# DI.net
KiCad netlist of a schematic drawn in Altium Designer
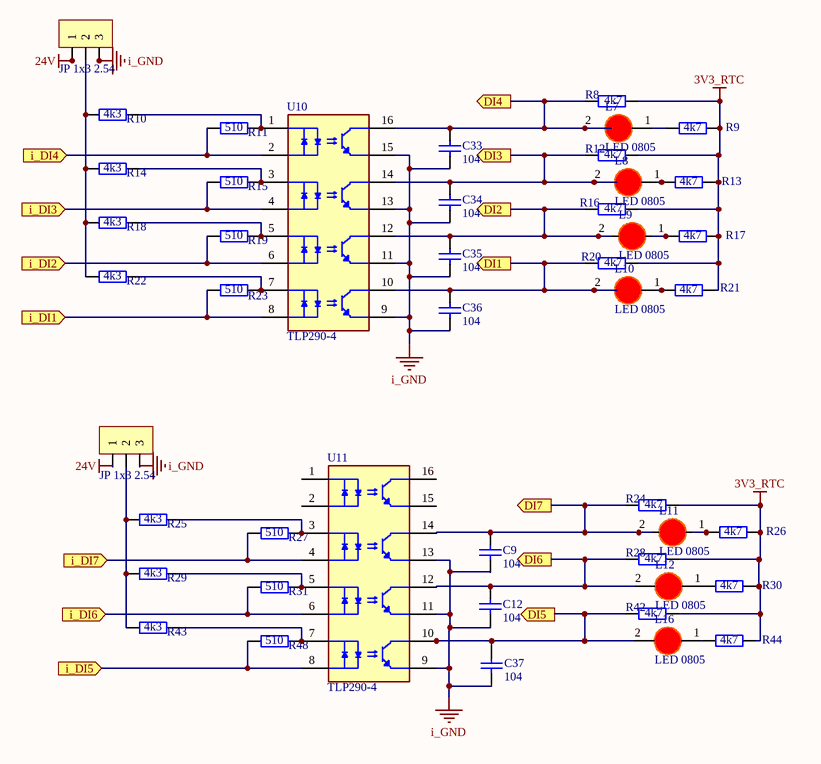
[diagram p0: DI.SchDoc]

(export (version "E")
  (design (tool "Eeschema 10.0.6"))
  (components
    (comp (ref "C9") (value "104") (footprint "0603_Cap") (libsource (lib "CMN") (part "Ceramic Capacitor")))
    (comp (ref "C12") (value "104") (footprint "0603_Cap") (libsource (lib "CMN") (part "Ceramic Capacitor")))
    (comp (ref "C33") (value "104") (footprint "0603_Cap") (libsource (lib "CMN") (part "Ceramic Capacitor")))
    (comp (ref "C34") (value "104") (footprint "0603_Cap") (libsource (lib "CMN") (part "Ceramic Capacitor")))
    (comp (ref "C35") (value "104") (footprint "0603_Cap") (libsource (lib "CMN") (part "Ceramic Capacitor")))
    (comp (ref "C36") (value "104") (footprint "0603_Cap") (libsource (lib "CMN") (part "Ceramic Capacitor")))
    (comp (ref "C37") (value "104") (footprint "0603_Cap") (libsource (lib "CMN") (part "Ceramic Capacitor")))
    (comp (ref "JP3")
      (value "JP 1x3 2.54")
      (footprint "JP 1x3 DT")
      (description "Cắm")
      (libsource (lib "Jump") (part "JP 1x3 2.54 Duc Thang"))
    )
    (comp (ref "JP4")
      (value "JP 1x3 2.54")
      (footprint "JP 1x3 DT")
      (description "Cắm")
      (libsource (lib "Jump") (part "JP 1x3 2.54 Duc Thang"))
    )
    (comp (ref "L7")
      (value "LED 0805")
      (footprint "LED-1206-Red")
      (description "Dán")
      (libsource (lib "Led") (part "LED 1206 Do"))
    )
    (comp (ref "L8")
      (value "LED 0805")
      (footprint "LED-1206-Red")
      (description "Dán")
      (libsource (lib "Led") (part "LED 1206 Do"))
    )
    (comp (ref "L9")
      (value "LED 0805")
      (footprint "LED-1206-Red")
      (description "Dán")
      (libsource (lib "Led") (part "LED 1206 Do"))
    )
    (comp (ref "L10")
      (value "LED 0805")
      (footprint "LED-1206-Red")
      (description "Dán")
      (libsource (lib "Led") (part "LED 1206 Do"))
    )
    (comp (ref "L11")
      (value "LED 0805")
      (footprint "LED-1206-Red")
      (description "Dán")
      (libsource (lib "Led") (part "LED 1206 Do"))
    )
    (comp (ref "L12")
      (value "LED 0805")
      (footprint "LED-1206-Red")
      (description "Dán")
      (libsource (lib "Led") (part "LED 1206 Do"))
    )
    (comp (ref "L16")
      (value "LED 0805")
      (footprint "LED-1206-Red")
      (description "Dán")
      (libsource (lib "Led") (part "LED 1206 Do"))
    )
    (comp (ref "R8") (value "4k7") (footprint "0603_Res") (libsource (lib "CMN") (part "Resistor")))
    (comp (ref "R9") (value "4k7") (footprint "0603_Res") (libsource (lib "CMN") (part "Resistor")))
    (comp (ref "R10") (value "4k3") (footprint "0603_Res") (libsource (lib "CMN") (part "Resistor")))
    (comp (ref "R11") (value "510") (footprint "0603_Res") (libsource (lib "CMN") (part "Resistor")))
    (comp (ref "R12") (value "4k7") (footprint "0603_Res") (libsource (lib "CMN") (part "Resistor")))
    (comp (ref "R13") (value "4k7") (footprint "0603_Res") (libsource (lib "CMN") (part "Resistor")))
    (comp (ref "R14") (value "4k3") (footprint "0603_Res") (libsource (lib "CMN") (part "Resistor")))
    (comp (ref "R15") (value "510") (footprint "0603_Res") (libsource (lib "CMN") (part "Resistor")))
    (comp (ref "R16") (value "4k7") (footprint "0603_Res") (libsource (lib "CMN") (part "Resistor")))
    (comp (ref "R17") (value "4k7") (footprint "0603_Res") (libsource (lib "CMN") (part "Resistor")))
    (comp (ref "R18") (value "4k3") (footprint "0603_Res") (libsource (lib "CMN") (part "Resistor")))
    (comp (ref "R19") (value "510") (footprint "0603_Res") (libsource (lib "CMN") (part "Resistor")))
    (comp (ref "R20") (value "4k7") (footprint "0603_Res") (libsource (lib "CMN") (part "Resistor")))
    (comp (ref "R21") (value "4k7") (footprint "0603_Res") (libsource (lib "CMN") (part "Resistor")))
    (comp (ref "R22") (value "4k3") (footprint "0603_Res") (libsource (lib "CMN") (part "Resistor")))
    (comp (ref "R23") (value "510") (footprint "0603_Res") (libsource (lib "CMN") (part "Resistor")))
    (comp (ref "R24") (value "4k7") (footprint "0603_Res") (libsource (lib "CMN") (part "Resistor")))
    (comp (ref "R25") (value "4k3") (footprint "0603_Res") (libsource (lib "CMN") (part "Resistor")))
    (comp (ref "R26") (value "4k7") (footprint "0603_Res") (libsource (lib "CMN") (part "Resistor")))
    (comp (ref "R27") (value "510") (footprint "0603_Res") (libsource (lib "CMN") (part "Resistor")))
    (comp (ref "R28") (value "4k7") (footprint "0603_Res") (libsource (lib "CMN") (part "Resistor")))
    (comp (ref "R29") (value "4k3") (footprint "0603_Res") (libsource (lib "CMN") (part "Resistor")))
    (comp (ref "R30") (value "4k7") (footprint "0603_Res") (libsource (lib "CMN") (part "Resistor")))
    (comp (ref "R31") (value "510") (footprint "0603_Res") (libsource (lib "CMN") (part "Resistor")))
    (comp (ref "R42") (value "4k7") (footprint "0603_Res") (libsource (lib "CMN") (part "Resistor")))
    (comp (ref "R43") (value "4k3") (footprint "0603_Res") (libsource (lib "CMN") (part "Resistor")))
    (comp (ref "R44") (value "4k7") (footprint "0603_Res") (libsource (lib "CMN") (part "Resistor")))
    (comp (ref "R48") (value "510") (footprint "0603_Res") (libsource (lib "CMN") (part "Resistor")))
    (comp (ref "U10")
      (value "TLP290-4")
      (footprint "OPTO_TLP290-4")
      (description "Optoisolator Transistor Output 2500Vrms 4 Channel 16-SO")
      (fields (field (name "MF") "Toshiba Semiconductor"))
      (libsource (lib "TLP290-4") (part "TLP290-4"))
    )
    (comp (ref "U11")
      (value "TLP290-4")
      (footprint "OPTO_TLP290-4")
      (description "Optoisolator Transistor Output 2500Vrms 4 Channel 16-SO")
      (fields (field (name "MF") "Toshiba Semiconductor"))
      (libsource (lib "TLP290-4") (part "TLP290-4"))
    )
  )
  (nets
    (net (code "1") (name "/DI1") (class "Default")
      (node (ref "C36") (pin "1") (pinfunction "1_1") (pintype "passive"))
      (node (ref "L10") (pin "2") (pinfunction "K_2") (pintype "passive"))
      (node (ref "R20") (pin "1") (pinfunction "1_1") (pintype "passive"))
      (node (ref "U10") (pin "10") (pinfunction "10_10") (pintype "passive"))
    )
    (net (code "2") (name "/DI2") (class "Default")
      (node (ref "C35") (pin "1") (pinfunction "1_1") (pintype "passive"))
      (node (ref "L9") (pin "2") (pinfunction "K_2") (pintype "passive"))
      (node (ref "R16") (pin "1") (pinfunction "1_1") (pintype "passive"))
      (node (ref "U10") (pin "12") (pinfunction "12_12") (pintype "passive"))
    )
    (net (code "3") (name "/DI3") (class "Default")
      (node (ref "C34") (pin "1") (pinfunction "1_1") (pintype "passive"))
      (node (ref "L8") (pin "2") (pinfunction "K_2") (pintype "passive"))
      (node (ref "R12") (pin "1") (pinfunction "1_1") (pintype "passive"))
      (node (ref "U10") (pin "14") (pinfunction "14_14") (pintype "passive"))
    )
    (net (code "4") (name "/DI4") (class "Default")
      (node (ref "C33") (pin "1") (pinfunction "1_1") (pintype "passive"))
      (node (ref "L7") (pin "2") (pinfunction "K_2") (pintype "passive"))
      (node (ref "R8") (pin "1") (pinfunction "1_1") (pintype "passive"))
      (node (ref "U10") (pin "16") (pinfunction "16_16") (pintype "passive"))
    )
    (net (code "5") (name "/DI5") (class "Default")
      (node (ref "C37") (pin "1") (pinfunction "1_1") (pintype "passive"))
      (node (ref "L16") (pin "2") (pinfunction "K_2") (pintype "passive"))
      (node (ref "R42") (pin "1") (pinfunction "1_1") (pintype "passive"))
      (node (ref "U11") (pin "10") (pinfunction "10_10") (pintype "passive"))
    )
    (net (code "6") (name "/DI6") (class "Default")
      (node (ref "C12") (pin "1") (pinfunction "1_1") (pintype "passive"))
      (node (ref "L12") (pin "2") (pinfunction "K_2") (pintype "passive"))
      (node (ref "R28") (pin "1") (pinfunction "1_1") (pintype "passive"))
      (node (ref "U11") (pin "12") (pinfunction "12_12") (pintype "passive"))
    )
    (net (code "7") (name "/DI7") (class "Default")
      (node (ref "C9") (pin "1") (pinfunction "1_1") (pintype "passive"))
      (node (ref "L11") (pin "2") (pinfunction "K_2") (pintype "passive"))
      (node (ref "R24") (pin "1") (pinfunction "1_1") (pintype "passive"))
      (node (ref "U11") (pin "14") (pinfunction "14_14") (pintype "passive"))
    )
    (net (code "8") (name "/i_DI1") (class "Default")
      (node (ref "R23") (pin "2") (pinfunction "2_2") (pintype "passive"))
      (node (ref "U10") (pin "8") (pinfunction "8_8") (pintype "passive"))
    )
    (net (code "9") (name "/i_DI2") (class "Default")
      (node (ref "R19") (pin "2") (pinfunction "2_2") (pintype "passive"))
      (node (ref "U10") (pin "6") (pinfunction "6_6") (pintype "passive"))
    )
    (net (code "10") (name "/i_DI3") (class "Default")
      (node (ref "R15") (pin "2") (pinfunction "2_2") (pintype "passive"))
      (node (ref "U10") (pin "4") (pinfunction "4_4") (pintype "passive"))
    )
    (net (code "11") (name "/i_DI4") (class "Default")
      (node (ref "R11") (pin "2") (pinfunction "2_2") (pintype "passive"))
      (node (ref "U10") (pin "2") (pinfunction "2_2") (pintype "passive"))
    )
    (net (code "12") (name "/i_DI5") (class "Default")
      (node (ref "R48") (pin "2") (pinfunction "2_2") (pintype "passive"))
      (node (ref "U11") (pin "8") (pinfunction "8_8") (pintype "passive"))
    )
    (net (code "13") (name "/i_DI6") (class "Default")
      (node (ref "R31") (pin "2") (pinfunction "2_2") (pintype "passive"))
      (node (ref "U11") (pin "6") (pinfunction "6_6") (pintype "passive"))
    )
    (net (code "14") (name "/i_DI7") (class "Default")
      (node (ref "R27") (pin "2") (pinfunction "2_2") (pintype "passive"))
      (node (ref "U11") (pin "4") (pinfunction "4_4") (pintype "passive"))
    )
    (net (code "15") (name "3V3_RTC") (class "Default")
      (node (ref "R12") (pin "2") (pinfunction "2_2") (pintype "passive"))
      (node (ref "R13") (pin "2") (pinfunction "2_2") (pintype "passive"))
      (node (ref "R16") (pin "2") (pinfunction "2_2") (pintype "passive"))
      (node (ref "R17") (pin "2") (pinfunction "2_2") (pintype "passive"))
      (node (ref "R20") (pin "2") (pinfunction "2_2") (pintype "passive"))
      (node (ref "R21") (pin "2") (pinfunction "2_2") (pintype "passive"))
      (node (ref "R24") (pin "2") (pinfunction "2_2") (pintype "passive"))
      (node (ref "R26") (pin "2") (pinfunction "2_2") (pintype "passive"))
      (node (ref "R28") (pin "2") (pinfunction "2_2") (pintype "passive"))
      (node (ref "R30") (pin "2") (pinfunction "2_2") (pintype "passive"))
      (node (ref "R42") (pin "2") (pinfunction "2_2") (pintype "passive"))
      (node (ref "R44") (pin "2") (pinfunction "2_2") (pintype "passive"))
      (node (ref "R8") (pin "2") (pinfunction "2_2") (pintype "passive"))
      (node (ref "R9") (pin "2") (pinfunction "2_2") (pintype "passive"))
    )
    (net (code "16") (name "24V") (class "Default")
      (node (ref "JP3") (pin "1") (pinfunction "1_1") (pintype "passive"))
      (node (ref "JP4") (pin "1") (pinfunction "1_1") (pintype "passive"))
    )
    (net (code "17") (name "Net-(JP3-Pad2)") (class "Default")
      (node (ref "JP3") (pin "2") (pinfunction "2_2") (pintype "passive"))
      (node (ref "R10") (pin "1") (pinfunction "1_1") (pintype "passive"))
      (node (ref "R14") (pin "1") (pinfunction "1_1") (pintype "passive"))
      (node (ref "R18") (pin "1") (pinfunction "1_1") (pintype "passive"))
      (node (ref "R22") (pin "1") (pinfunction "1_1") (pintype "passive"))
    )
    (net (code "18") (name "Net-(JP4-Pad2)") (class "Default")
      (node (ref "JP4") (pin "2") (pinfunction "2_2") (pintype "passive"))
      (node (ref "R25") (pin "1") (pinfunction "1_1") (pintype "passive"))
      (node (ref "R29") (pin "1") (pinfunction "1_1") (pintype "passive"))
      (node (ref "R43") (pin "1") (pinfunction "1_1") (pintype "passive"))
    )
    (net (code "19") (name "Net-(L7-A)") (class "Default")
      (node (ref "L7") (pin "1") (pinfunction "A_1") (pintype "passive"))
      (node (ref "R9") (pin "1") (pinfunction "1_1") (pintype "passive"))
    )
    (net (code "20") (name "Net-(L8-A)") (class "Default")
      (node (ref "L8") (pin "1") (pinfunction "A_1") (pintype "passive"))
      (node (ref "R13") (pin "1") (pinfunction "1_1") (pintype "passive"))
    )
    (net (code "21") (name "Net-(L9-A)") (class "Default")
      (node (ref "L9") (pin "1") (pinfunction "A_1") (pintype "passive"))
      (node (ref "R17") (pin "1") (pinfunction "1_1") (pintype "passive"))
    )
    (net (code "22") (name "Net-(L10-A)") (class "Default")
      (node (ref "L10") (pin "1") (pinfunction "A_1") (pintype "passive"))
      (node (ref "R21") (pin "1") (pinfunction "1_1") (pintype "passive"))
    )
    (net (code "23") (name "Net-(L11-A)") (class "Default")
      (node (ref "L11") (pin "1") (pinfunction "A_1") (pintype "passive"))
      (node (ref "R26") (pin "1") (pinfunction "1_1") (pintype "passive"))
    )
    (net (code "24") (name "Net-(L12-A)") (class "Default")
      (node (ref "L12") (pin "1") (pinfunction "A_1") (pintype "passive"))
      (node (ref "R30") (pin "1") (pinfunction "1_1") (pintype "passive"))
    )
    (net (code "25") (name "Net-(L16-A)") (class "Default")
      (node (ref "L16") (pin "1") (pinfunction "A_1") (pintype "passive"))
      (node (ref "R44") (pin "1") (pinfunction "1_1") (pintype "passive"))
    )
    (net (code "26") (name "Net-(R10-Pad2)") (class "Default")
      (node (ref "R10") (pin "2") (pinfunction "2_2") (pintype "passive"))
      (node (ref "R11") (pin "1") (pinfunction "1_1") (pintype "passive"))
      (node (ref "U10") (pin "1") (pinfunction "1_1") (pintype "passive"))
    )
    (net (code "27") (name "Net-(R14-Pad2)") (class "Default")
      (node (ref "R14") (pin "2") (pinfunction "2_2") (pintype "passive"))
      (node (ref "R15") (pin "1") (pinfunction "1_1") (pintype "passive"))
      (node (ref "U10") (pin "3") (pinfunction "3_3") (pintype "passive"))
    )
    (net (code "28") (name "Net-(R18-Pad2)") (class "Default")
      (node (ref "R18") (pin "2") (pinfunction "2_2") (pintype "passive"))
      (node (ref "R19") (pin "1") (pinfunction "1_1") (pintype "passive"))
      (node (ref "U10") (pin "5") (pinfunction "5_5") (pintype "passive"))
    )
    (net (code "29") (name "Net-(R22-Pad2)") (class "Default")
      (node (ref "R22") (pin "2") (pinfunction "2_2") (pintype "passive"))
      (node (ref "R23") (pin "1") (pinfunction "1_1") (pintype "passive"))
      (node (ref "U10") (pin "7") (pinfunction "7_7") (pintype "passive"))
    )
    (net (code "30") (name "Net-(R25-Pad2)") (class "Default")
      (node (ref "R25") (pin "2") (pinfunction "2_2") (pintype "passive"))
      (node (ref "R27") (pin "1") (pinfunction "1_1") (pintype "passive"))
      (node (ref "U11") (pin "3") (pinfunction "3_3") (pintype "passive"))
    )
    (net (code "31") (name "Net-(R29-Pad2)") (class "Default")
      (node (ref "R29") (pin "2") (pinfunction "2_2") (pintype "passive"))
      (node (ref "R31") (pin "1") (pinfunction "1_1") (pintype "passive"))
      (node (ref "U11") (pin "5") (pinfunction "5_5") (pintype "passive"))
    )
    (net (code "32") (name "Net-(R43-Pad2)") (class "Default")
      (node (ref "R43") (pin "2") (pinfunction "2_2") (pintype "passive"))
      (node (ref "R48") (pin "1") (pinfunction "1_1") (pintype "passive"))
      (node (ref "U11") (pin "7") (pinfunction "7_7") (pintype "passive"))
    )
    (net (code "33") (name "i_GND") (class "Default")
      (node (ref "C12") (pin "2") (pinfunction "2_2") (pintype "passive"))
      (node (ref "C33") (pin "2") (pinfunction "2_2") (pintype "passive"))
      (node (ref "C34") (pin "2") (pinfunction "2_2") (pintype "passive"))
      (node (ref "C35") (pin "2") (pinfunction "2_2") (pintype "passive"))
      (node (ref "C36") (pin "2") (pinfunction "2_2") (pintype "passive"))
      (node (ref "C37") (pin "2") (pinfunction "2_2") (pintype "passive"))
      (node (ref "C9") (pin "2") (pinfunction "2_2") (pintype "passive"))
      (node (ref "JP3") (pin "3") (pinfunction "3_3") (pintype "passive"))
      (node (ref "JP4") (pin "3") (pinfunction "3_3") (pintype "passive"))
      (node (ref "U10") (pin "11") (pinfunction "11_11") (pintype "passive"))
      (node (ref "U10") (pin "13") (pinfunction "13_13") (pintype "passive"))
      (node (ref "U10") (pin "15") (pinfunction "15_15") (pintype "passive"))
      (node (ref "U10") (pin "9") (pinfunction "9_9") (pintype "passive"))
      (node (ref "U11") (pin "11") (pinfunction "11_11") (pintype "passive"))
      (node (ref "U11") (pin "13") (pinfunction "13_13") (pintype "passive"))
      (node (ref "U11") (pin "9") (pinfunction "9_9") (pintype "passive"))
    )
    (net (code "34") (name "unconnected-(U11-Pad1)") (class "Default")
      (node (ref "U11") (pin "1") (pinfunction "1_1") (pintype "passive"))
    )
    (net (code "35") (name "unconnected-(U11-Pad2)") (class "Default")
      (node (ref "U11") (pin "2") (pinfunction "2_2") (pintype "passive"))
    )
    (net (code "36") (name "unconnected-(U11-Pad15)") (class "Default")
      (node (ref "U11") (pin "15") (pinfunction "15_15") (pintype "passive"))
    )
    (net (code "37") (name "unconnected-(U11-Pad16)") (class "Default")
      (node (ref "U11") (pin "16") (pinfunction "16_16") (pintype "passive"))
    )
  )
)
